# LD-ShouShi-V1_7.net
KiCad netlist of a schematic drawn in Altium Designer
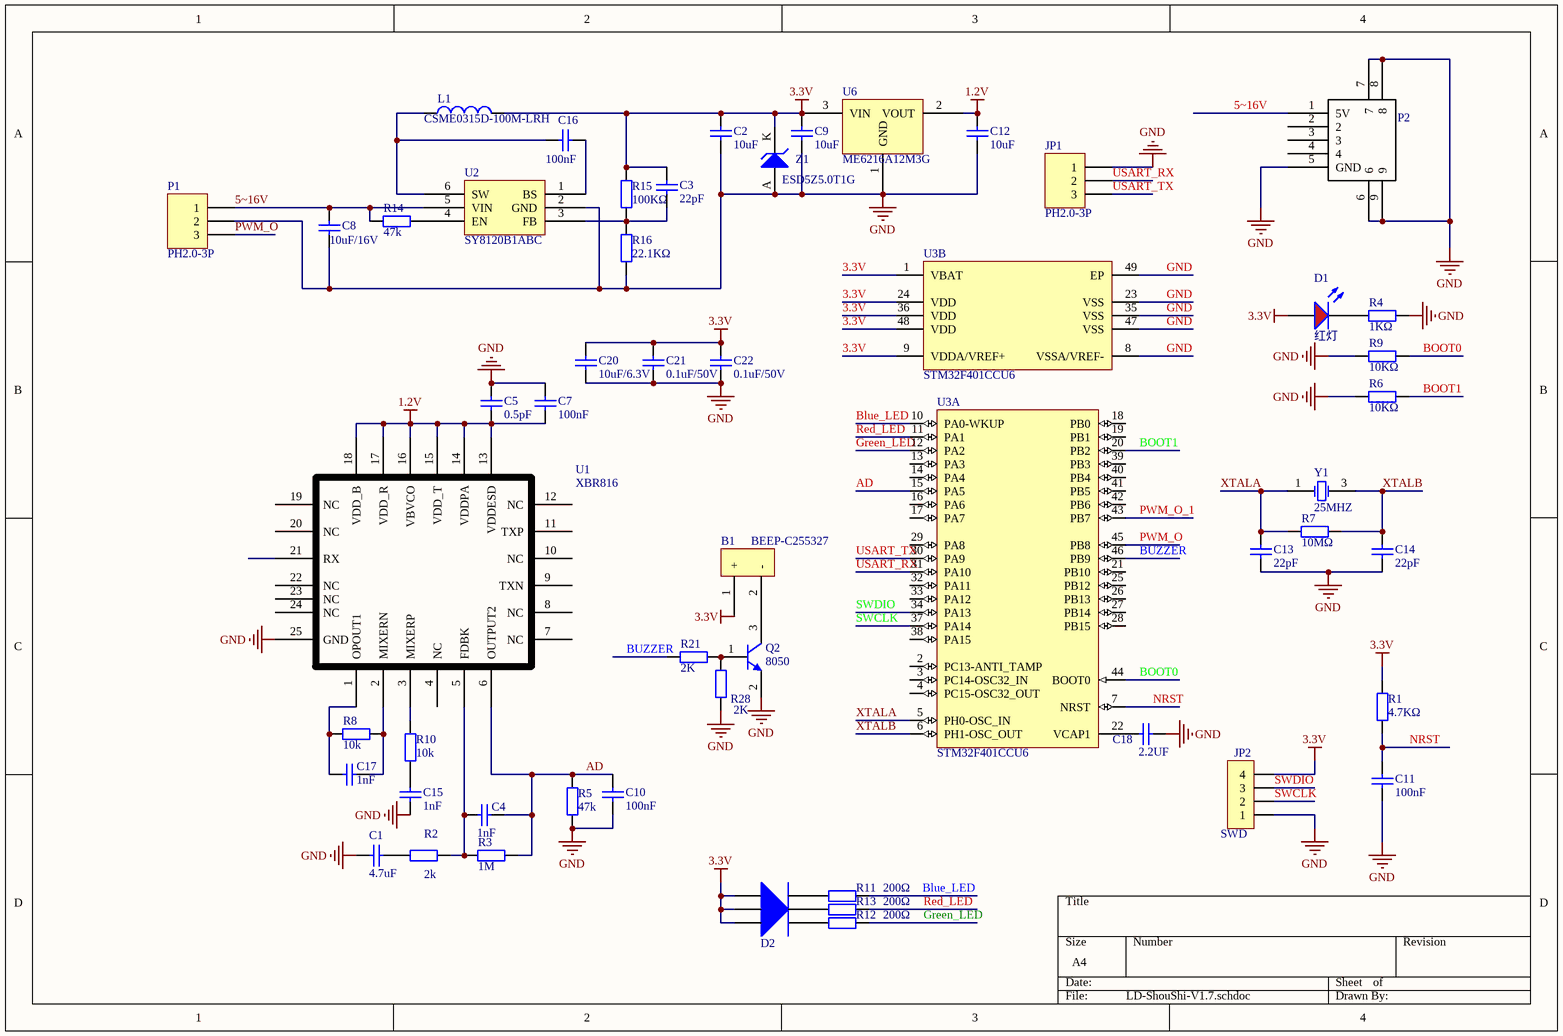
[diagram p0: LD-ShouShi-V1.7.schdoc]

(export (version "E")
  (design (tool "Eeschema 10.0.6"))
  (components
    (comp (ref "B1")
      (value "BEEP-C255327")
      (footprint "C255327-Beep")
      (libsource (lib "PCB_Project1") (part "BEEP"))
    )
    (comp (ref "C1")
      (value "4.7uF")
      (footprint "C0402")
      (description "Capacitor")
      (fields (field (name "PUBLISHER") "Altium Limited"))
      (libsource (lib "Miscellaneous Devices") (part "Cap"))
    )
    (comp (ref "C2")
      (value "10uF")
      (footprint "LC-0402_C")
      (description "贴片电容")
      (libsource (lib "Miscellaneous Devices LC") (part "0402 10uF (106) 20% 6.3V"))
    )
    (comp (ref "C3")
      (value "22pF")
      (footprint "LC-0402_C")
      (description "贴片电容")
      (libsource (lib "Miscellaneous Devices LC") (part "0402 22pF (220) 5% 50V"))
    )
    (comp (ref "C4")
      (value "1nF")
      (footprint "C0402")
      (description "Capacitor")
      (fields (field (name "PUBLISHER") "Altium Limited"))
      (libsource (lib "Miscellaneous Devices") (part "Cap"))
    )
    (comp (ref "C5")
      (value "0.5pF")
      (footprint "C0402")
      (description "Capacitor")
      (fields (field (name "PUBLISHER") "Altium Limited"))
      (libsource (lib "Miscellaneous Devices") (part "Cap"))
    )
    (comp (ref "C7")
      (value "100nF")
      (footprint "C0402")
      (description "Capacitor")
      (fields (field (name "PUBLISHER") "Altium Limited"))
      (libsource (lib "Miscellaneous Devices") (part "Cap"))
    )
    (comp (ref "C8")
      (value "10uF/16V")
      (footprint "C0805")
      (description "Capacitor")
      (fields (field (name "PUBLISHER") "Altium Limited"))
      (libsource (lib "Miscellaneous Devices") (part "Cap"))
    )
    (comp (ref "C9")
      (value "10uF")
      (footprint "LC-0402_C")
      (description "贴片电容")
      (libsource (lib "Miscellaneous Devices LC") (part "0402 10uF (106) 20% 6.3V"))
    )
    (comp (ref "C10")
      (value "100nF")
      (footprint "C0402")
      (description "Capacitor")
      (fields (field (name "PUBLISHER") "Altium Limited"))
      (libsource (lib "Miscellaneous Devices") (part "Cap"))
    )
    (comp (ref "C11")
      (value "100nF")
      (footprint "LC-0402_C")
      (description "贴片电容")
      (libsource (lib "Miscellaneous Devices LC") (part "0402 100nF (104) 10% 16V"))
    )
    (comp (ref "C12")
      (value "10uF")
      (footprint "LC-0402_C")
      (description "贴片电容")
      (libsource (lib "Miscellaneous Devices LC") (part "0402 10uF (106) 20% 6.3V"))
    )
    (comp (ref "C13")
      (value "22pF")
      (footprint "LC-0402_C")
      (description "贴片电容")
      (libsource (lib "Cap") (part "0402 22pF (220) 5% 50V"))
    )
    (comp (ref "C14")
      (value "22pF")
      (footprint "LC-0402_C")
      (description "贴片电容")
      (libsource (lib "Cap") (part "0402 22pF (220) 5% 50V"))
    )
    (comp (ref "C15")
      (value "1nF")
      (footprint "C0402")
      (description "Capacitor")
      (fields (field (name "PUBLISHER") "Altium Limited"))
      (libsource (lib "Miscellaneous Devices") (part "Cap"))
    )
    (comp (ref "C16")
      (value "100nF")
      (footprint "C0402")
      (description "Capacitor")
      (fields (field (name "PUBLISHER") "Altium Limited"))
      (libsource (lib "Miscellaneous Devices") (part "Cap"))
    )
    (comp (ref "C17")
      (value "1nF")
      (footprint "C0402")
      (description "Capacitor")
      (fields (field (name "PUBLISHER") "Altium Limited"))
      (libsource (lib "Miscellaneous Devices") (part "Cap"))
    )
    (comp (ref "C18")
      (value "2.2UF")
      (footprint "LC-0402_C")
      (description "贴片电容")
      (libsource (lib "Cap") (part "0402 2.2nF (222) 10% 50V"))
    )
    (comp (ref "C20")
      (value "10uF/6.3V")
      (footprint "LC-0402_C")
      (description "贴片电容")
      (libsource (lib "Miscellaneous Devices LC") (part "0402 10uF (106) 20% 6.3V"))
    )
    (comp (ref "C21")
      (value "0.1uF/50V")
      (footprint "LC-0402_C")
      (description "贴片电容")
      (libsource (lib "Miscellaneous Devices LC") (part "0402 10uF (106) 20% 6.3V"))
    )
    (comp (ref "C22")
      (value "0.1uF/50V")
      (footprint "LC-0402_C")
      (description "贴片电容")
      (libsource (lib "Miscellaneous Devices LC") (part "0402 10uF (106) 20% 6.3V"))
    )
    (comp (ref "D1")
      (value "红灯")
      (footprint "LC-0603_LED_S1")
      (description "发光二极管")
      (libsource (lib "Miscellaneous Devices LC") (part "0603 红灯"))
    )
    (comp (ref "D2") (value "led三色共阴极灯") (footprint "三色灯") (libsource (lib "微波红外双鉴电路") (part "led三色共阴极灯")))
    (comp (ref "JP1")
      (value "PH2.0-3P")
      (footprint "1X3-2.54")
      (description "Header, 3-Pin")
      (fields (field (name "PUBLISHER") "Altium Limited"))
      (libsource (lib "Miscellaneous Connectors") (part "Header 3"))
    )
    (comp (ref "JP2")
      (value "SWD")
      (footprint "SIP4-2.54")
      (description "4P接插件")
      (fields (field (name "版权归属") "源创客"))
      (libsource (lib "STM32F407_CORE_BOARD") (part "Header 4"))
    )
    (comp (ref "L1")
      (value "CSME0315D-100M-LRH")
      (footprint "PRS3015")
      (description "Inductor")
      (fields (field (name "PUBLISHER") "Altium Limited"))
      (libsource (lib "Miscellaneous Devices") (part "Inductor"))
    )
    (comp (ref "P1")
      (value "PH2.0-3P")
      (footprint "PH2.0-3P")
      (description "Header, 3-Pin")
      (fields (field (name "PUBLISHER") "Altium Limited"))
      (libsource (lib "Miscellaneous Connectors") (part "Header 3"))
    )
    (comp (ref "P2") (value "MINIUSB") (footprint "miniusb") (libsource (lib "调色灯") (part "MINIUSB-M")))
    (comp (ref "Q2")
      (value "8050")
      (footprint "SOT-23")
      (description "NPN General Purpose Amplifier")
      (fields (field (name "PUBLISHER") "Altium Limited"))
      (libsource (lib "圆形报警器NEW-V2.0") (part "2N3904"))
    )
    (comp (ref "R1")
      (value "4.7KΩ")
      (footprint "LC-0402_R")
      (description "贴片电阻")
      (libsource (lib "Miscellaneous Devices LC") (part "0402 4.7KΩ (4701) 1%"))
    )
    (comp (ref "R2")
      (value "2k")
      (footprint "R0402")
      (description "Resistor")
      (fields (field (name "PUBLISHER") "Altium Limited"))
      (libsource (lib "") (part "Res2_2"))
    )
    (comp (ref "R3")
      (value "1M")
      (footprint "R0402")
      (description "Resistor")
      (fields (field (name "PUBLISHER") "Altium Limited"))
      (libsource (lib "") (part "Res2_1"))
    )
    (comp (ref "R4")
      (value "1KΩ")
      (footprint "LC-0402_R")
      (description "贴片电阻")
      (libsource (lib "Miscellaneous Devices LC") (part "0402 1KΩ (1001) 1%"))
    )
    (comp (ref "R5")
      (value "47k")
      (footprint "R0402")
      (description "Resistor")
      (fields (field (name "PUBLISHER") "Altium Limited"))
      (libsource (lib "Miscellaneous Devices") (part "Res2"))
    )
    (comp (ref "R6")
      (value "10KΩ")
      (footprint "LC-0402_R")
      (description "贴片电阻")
      (libsource (lib "Miscellaneous Devices LC") (part "0402 10KΩ (1002) 1%"))
    )
    (comp (ref "R7")
      (value "10MΩ")
      (footprint "LC-0402_R")
      (description "贴片电阻")
      (libsource (lib "Miscellaneous Devices LC") (part "0402 10MΩ (1005) 1%"))
    )
    (comp (ref "R8")
      (value "10k")
      (footprint "R0402")
      (description "Resistor")
      (fields (field (name "PUBLISHER") "Altium Limited"))
      (libsource (lib "") (part "Res2_1"))
    )
    (comp (ref "R9")
      (value "10KΩ")
      (footprint "LC-0402_R")
      (description "贴片电阻")
      (libsource (lib "Miscellaneous Devices LC") (part "0402 10KΩ (1002) 1%"))
    )
    (comp (ref "R10")
      (value "10k")
      (footprint "R0402")
      (description "Resistor")
      (fields (field (name "PUBLISHER") "Altium Limited"))
      (libsource (lib "Miscellaneous Devices") (part "Res2"))
    )
    (comp (ref "R11")
      (value "200Ω")
      (footprint "LC-0402_R")
      (description "贴片电阻")
      (libsource (lib "Miscellaneous Devices LC") (part "0402 200Ω (2000) 1%"))
    )
    (comp (ref "R12")
      (value "200Ω")
      (footprint "LC-0402_R")
      (description "贴片电阻")
      (libsource (lib "Miscellaneous Devices LC") (part "0402 200Ω (2000) 1%"))
    )
    (comp (ref "R13")
      (value "200Ω")
      (footprint "LC-0402_R")
      (description "贴片电阻")
      (libsource (lib "Miscellaneous Devices LC") (part "0402 200Ω (2000) 1%"))
    )
    (comp (ref "R14")
      (value "47k")
      (footprint "R0402")
      (description "Resistor")
      (fields (field (name "PUBLISHER") "Altium Limited"))
      (libsource (lib "") (part "Res2_1"))
    )
    (comp (ref "R15")
      (value "100KΩ")
      (footprint "LC-0402_R")
      (description "贴片电阻")
      (libsource (lib "Miscellaneous Devices LC") (part "0402 100KΩ (1003) 1%"))
    )
    (comp (ref "R16")
      (value "22.1KΩ")
      (footprint "LC-0402_R")
      (description "贴片电阻")
      (libsource (lib "Miscellaneous Devices LC") (part "0402 22KΩ (2202) 1%"))
    )
    (comp (ref "R21")
      (value "2K")
      (footprint "R0402")
      (description "Resistor")
      (fields (field (name "PUBLISHER") "Altium Limited"))
      (libsource (lib "*") (part "Res2"))
    )
    (comp (ref "R28")
      (value "2K")
      (footprint "R0402")
      (description "Resistor")
      (fields (field (name "PUBLISHER") "Altium Limited"))
      (libsource (lib "") (part "Res2_1"))
    )
    (comp (ref "U1") (value "XBR816") (footprint "QFN24-1") (libsource (lib "Schlib1") (part "XBR1000_24_1")))
    (comp (ref "U2") (value "SY8120B1ABC") (footprint "SOT23-6") (libsource (lib "Schlib1") (part "H9108")))
    (comp (ref "U3")
      (value "STM32F401CCU6")
      (footprint "UFQFPN-48_L7.0-W7.0-P0.50-BL-EP")
      (fields (field (name "MANUFACTURER") "STMicroelectronics"))
      (libsource (lib "STMicroelectronics STM32 F4") (part "STM32F401CCU6"))
    )
    (comp (ref "U6") (value "ME6216A12M3G") (footprint "SOT-23") (libsource (lib "Schlib1") (part "SSP6206")))
    (comp (ref "Y1")
      (value "25MHZ")
      (footprint "OSC-SMD_4P-L2.0-W1.6-BL")
      (description "贴片晶振")
      (libsource (lib "CrystalOscillator") (part "SMD-3225_4P  25MHZ 12PF 10PPM"))
    )
    (comp (ref "Z1")
      (value "ESD5Z5.0T1G")
      (footprint "SOD523")
      (description "Zener Diode")
      (fields (field (name "PUBLISHER") "Altium Limited"))
      (libsource (lib "Miscellaneous Devices") (part "D Zener"))
    )
  )
  (nets
    (net (code "1") (name "/5~16V") (class "Default")
      (node (ref "C8") (pin "1") (pinfunction "1_1") (pintype "passive"))
      (node (ref "P1") (pin "1") (pinfunction "1_1") (pintype "passive"))
      (node (ref "P2") (pin "1") (pinfunction "5V_1") (pintype "passive"))
      (node (ref "R14") (pin "2") (pinfunction "2_2") (pintype "passive"))
      (node (ref "U2") (pin "5") (pinfunction "VIN_5") (pintype "passive"))
    )
    (net (code "2") (name "/AD") (class "Default")
      (node (ref "C10") (pin "1") (pinfunction "1_1") (pintype "passive"))
      (node (ref "C4") (pin "1") (pinfunction "1_1") (pintype "passive"))
      (node (ref "R3") (pin "1") (pinfunction "1_1") (pintype "passive"))
      (node (ref "R5") (pin "1") (pinfunction "1_1") (pintype "passive"))
      (node (ref "U1") (pin "6") (pinfunction "OUTPUT2_6") (pintype "passive"))
      (node (ref "U3") (pin "15") (pinfunction "PA5_15") (pintype "bidirectional"))
    )
    (net (code "3") (name "/BOOT0") (class "Default")
      (node (ref "R9") (pin "2") (pinfunction "2_2") (pintype "passive"))
      (node (ref "U3") (pin "44") (pinfunction "BOOT0_44") (pintype "input"))
    )
    (net (code "4") (name "/BOOT1") (class "Default")
      (node (ref "R6") (pin "2") (pinfunction "2_2") (pintype "passive"))
      (node (ref "U3") (pin "20") (pinfunction "PB2_20") (pintype "bidirectional"))
    )
    (net (code "5") (name "/BUZZER") (class "Default")
      (node (ref "R21") (pin "1") (pinfunction "1_1") (pintype "passive"))
      (node (ref "U3") (pin "46") (pinfunction "PB9_46") (pintype "bidirectional"))
    )
    (net (code "6") (name "/Blue_LED") (class "Default")
      (node (ref "R11") (pin "2") (pinfunction "2_2") (pintype "passive"))
      (node (ref "U3") (pin "10") (pinfunction "PA0-WKUP_10") (pintype "bidirectional"))
    )
    (net (code "7") (name "/Green_LED") (class "Default")
      (node (ref "R12") (pin "2") (pinfunction "2_2") (pintype "passive"))
      (node (ref "U3") (pin "12") (pinfunction "PA2_12") (pintype "bidirectional"))
    )
    (net (code "8") (name "/NRST") (class "Default")
      (node (ref "C11") (pin "2") (pinfunction "2_2") (pintype "passive"))
      (node (ref "R1") (pin "1") (pinfunction "1_1") (pintype "passive"))
      (node (ref "U3") (pin "7") (pinfunction "NRST_7") (pintype "bidirectional"))
    )
    (net (code "9") (name "/PWM_O") (class "Default")
      (node (ref "P1") (pin "3") (pinfunction "3_3") (pintype "passive"))
      (node (ref "U3") (pin "45") (pinfunction "PB8_45") (pintype "bidirectional"))
    )
    (net (code "10") (name "/PWM_O_1") (class "Default")
      (node (ref "U3") (pin "43") (pinfunction "PB7_43") (pintype "bidirectional"))
    )
    (net (code "11") (name "/Red_LED") (class "Default")
      (node (ref "R13") (pin "2") (pinfunction "2_2") (pintype "passive"))
      (node (ref "U3") (pin "11") (pinfunction "PA1_11") (pintype "bidirectional"))
    )
    (net (code "12") (name "/SWCLK") (class "Default")
      (node (ref "JP2") (pin "2") (pinfunction "2_2") (pintype "passive"))
      (node (ref "U3") (pin "37") (pinfunction "PA14_37") (pintype "bidirectional"))
    )
    (net (code "13") (name "/SWDIO") (class "Default")
      (node (ref "JP2") (pin "3") (pinfunction "3_3") (pintype "passive"))
      (node (ref "U3") (pin "34") (pinfunction "PA13_34") (pintype "bidirectional"))
    )
    (net (code "14") (name "/USART_RX") (class "Default")
      (node (ref "JP1") (pin "2") (pinfunction "2_2") (pintype "passive"))
      (node (ref "U3") (pin "31") (pinfunction "PA10_31") (pintype "bidirectional"))
    )
    (net (code "15") (name "/USART_TX") (class "Default")
      (node (ref "JP1") (pin "3") (pinfunction "3_3") (pintype "passive"))
      (node (ref "U3") (pin "30") (pinfunction "PA9_30") (pintype "bidirectional"))
    )
    (net (code "16") (name "/XTALA") (class "Default")
      (node (ref "C13") (pin "2") (pinfunction "2_2") (pintype "passive"))
      (node (ref "R7") (pin "1") (pinfunction "1_1") (pintype "passive"))
      (node (ref "U3") (pin "5") (pinfunction "PH0-OSC_IN_5") (pintype "bidirectional"))
      (node (ref "Y1") (pin "1") (pinfunction "OSC1_1") (pintype "passive"))
    )
    (net (code "17") (name "/XTALB") (class "Default")
      (node (ref "C14") (pin "2") (pinfunction "2_2") (pintype "passive"))
      (node (ref "R7") (pin "2") (pinfunction "2_2") (pintype "passive"))
      (node (ref "U3") (pin "6") (pinfunction "PH1-OSC_OUT_6") (pintype "bidirectional"))
      (node (ref "Y1") (pin "3") (pinfunction "OSC2_3") (pintype "passive"))
    )
    (net (code "18") (name "1.2V") (class "Default")
      (node (ref "C12") (pin "2") (pinfunction "2_2") (pintype "passive"))
      (node (ref "C5") (pin "1") (pinfunction "1_1") (pintype "passive"))
      (node (ref "C7") (pin "1") (pinfunction "1_1") (pintype "passive"))
      (node (ref "U1") (pin "13") (pinfunction "VDDESD_13") (pintype "passive"))
      (node (ref "U1") (pin "14") (pinfunction "VDDPA_14") (pintype "passive"))
      (node (ref "U1") (pin "15") (pinfunction "VDD_T_15") (pintype "passive"))
      (node (ref "U1") (pin "16") (pinfunction "VBVCO_16") (pintype "passive"))
      (node (ref "U1") (pin "17") (pinfunction "VDD_R_17") (pintype "passive"))
      (node (ref "U1") (pin "18") (pinfunction "VDD_B_18") (pintype "passive"))
      (node (ref "U6") (pin "2") (pinfunction "VOUT_2") (pintype "passive"))
    )
    (net (code "19") (name "3.3V") (class "Default")
      (node (ref "B1") (pin "1") (pinfunction "+_1") (pintype "passive"))
      (node (ref "C2") (pin "2") (pinfunction "2_2") (pintype "passive"))
      (node (ref "C20") (pin "2") (pinfunction "2_2") (pintype "passive"))
      (node (ref "C21") (pin "2") (pinfunction "2_2") (pintype "passive"))
      (node (ref "C22") (pin "2") (pinfunction "2_2") (pintype "passive"))
      (node (ref "C3") (pin "2") (pinfunction "2_2") (pintype "passive"))
      (node (ref "C9") (pin "2") (pinfunction "2_2") (pintype "passive"))
      (node (ref "D1") (pin "A") (pinfunction "A_A") (pintype "passive"))
      (node (ref "D2") (pin "1") (pinfunction "A+_1") (pintype "passive"))
      (node (ref "D2") (pin "2") (pinfunction "B+_2") (pintype "passive"))
      (node (ref "D2") (pin "3") (pinfunction "C+_3") (pintype "passive"))
      (node (ref "JP2") (pin "4") (pinfunction "4_4") (pintype "passive"))
      (node (ref "L1") (pin "2") (pinfunction "2_2") (pintype "passive"))
      (node (ref "R1") (pin "2") (pinfunction "2_2") (pintype "passive"))
      (node (ref "R15") (pin "2") (pinfunction "2_2") (pintype "passive"))
      (node (ref "U3") (pin "1") (pinfunction "VBAT_1") (pintype "power_in"))
      (node (ref "U3") (pin "24") (pinfunction "VDD_24") (pintype "power_in"))
      (node (ref "U3") (pin "36") (pinfunction "VDD_36") (pintype "power_in"))
      (node (ref "U3") (pin "48") (pinfunction "VDD_48") (pintype "power_in"))
      (node (ref "U3") (pin "9") (pinfunction "VDDA/VREF+_9") (pintype "power_in"))
      (node (ref "U6") (pin "3") (pinfunction "VIN_3") (pintype "passive"))
      (node (ref "Z1") (pin "K") (pinfunction "K_K") (pintype "passive"))
    )
    (net (code "20") (name "GND") (class "Default")
      (node (ref "C1") (pin "2") (pinfunction "2_2") (pintype "passive"))
      (node (ref "C10") (pin "2") (pinfunction "2_2") (pintype "passive"))
      (node (ref "C11") (pin "1") (pinfunction "1_1") (pintype "passive"))
      (node (ref "C12") (pin "1") (pinfunction "1_1") (pintype "passive"))
      (node (ref "C13") (pin "1") (pinfunction "1_1") (pintype "passive"))
      (node (ref "C14") (pin "1") (pinfunction "1_1") (pintype "passive"))
      (node (ref "C15") (pin "1") (pinfunction "1_1") (pintype "passive"))
      (node (ref "C18") (pin "2") (pinfunction "2_2") (pintype "passive"))
      (node (ref "C2") (pin "1") (pinfunction "1_1") (pintype "passive"))
      (node (ref "C20") (pin "1") (pinfunction "1_1") (pintype "passive"))
      (node (ref "C21") (pin "1") (pinfunction "1_1") (pintype "passive"))
      (node (ref "C22") (pin "1") (pinfunction "1_1") (pintype "passive"))
      (node (ref "C5") (pin "2") (pinfunction "2_2") (pintype "passive"))
      (node (ref "C7") (pin "2") (pinfunction "2_2") (pintype "passive"))
      (node (ref "C8") (pin "2") (pinfunction "2_2") (pintype "passive"))
      (node (ref "C9") (pin "1") (pinfunction "1_1") (pintype "passive"))
      (node (ref "JP1") (pin "1") (pinfunction "1_1") (pintype "passive"))
      (node (ref "JP2") (pin "1") (pinfunction "1_1") (pintype "passive"))
      (node (ref "P1") (pin "2") (pinfunction "2_2") (pintype "passive"))
      (node (ref "P2") (pin "5") (pinfunction "GND_5") (pintype "passive"))
      (node (ref "P2") (pin "6") (pinfunction "6_6") (pintype "passive"))
      (node (ref "P2") (pin "7") (pinfunction "7_7") (pintype "passive"))
      (node (ref "P2") (pin "8") (pinfunction "8_8") (pintype "passive"))
      (node (ref "P2") (pin "9") (pinfunction "9_9") (pintype "passive"))
      (node (ref "Q2") (pin "2") (pinfunction "E_2") (pintype "passive"))
      (node (ref "R16") (pin "2") (pinfunction "2_2") (pintype "passive"))
      (node (ref "R28") (pin "1") (pinfunction "1_1") (pintype "passive"))
      (node (ref "R4") (pin "1") (pinfunction "1_1") (pintype "passive"))
      (node (ref "R5") (pin "2") (pinfunction "2_2") (pintype "passive"))
      (node (ref "R6") (pin "1") (pinfunction "1_1") (pintype "passive"))
      (node (ref "R9") (pin "1") (pinfunction "1_1") (pintype "passive"))
      (node (ref "U1") (pin "25") (pinfunction "GND_25") (pintype "passive"))
      (node (ref "U2") (pin "2") (pinfunction "GND_2") (pintype "passive"))
      (node (ref "U3") (pin "23") (pinfunction "VSS_23") (pintype "power_in"))
      (node (ref "U3") (pin "35") (pinfunction "VSS_35") (pintype "power_in"))
      (node (ref "U3") (pin "47") (pinfunction "VSS_47") (pintype "power_in"))
      (node (ref "U3") (pin "49") (pinfunction "EP_49") (pintype "power_in"))
      (node (ref "U3") (pin "8") (pinfunction "VSSA/VREF-_8") (pintype "power_in"))
      (node (ref "U6") (pin "1") (pinfunction "GND_1") (pintype "passive"))
      (node (ref "Z1") (pin "A") (pinfunction "A_A") (pintype "passive"))
    )
    (net (code "21") (name "Net-(B1--)") (class "Default")
      (node (ref "B1") (pin "2") (pinfunction "-_2") (pintype "passive"))
      (node (ref "Q2") (pin "3") (pinfunction "C_3") (pintype "passive"))
    )
    (net (code "22") (name "Net-(C1-Pad1)") (class "Default")
      (node (ref "C1") (pin "1") (pinfunction "1_1") (pintype "passive"))
      (node (ref "R2") (pin "1") (pinfunction "1_1") (pintype "passive"))
    )
    (net (code "23") (name "Net-(C15-Pad2)") (class "Default")
      (node (ref "C15") (pin "2") (pinfunction "2_2") (pintype "passive"))
      (node (ref "R10") (pin "2") (pinfunction "2_2") (pintype "passive"))
    )
    (net (code "24") (name "Net-(D1-PadK)") (class "Default")
      (node (ref "D1") (pin "K") (pinfunction "K_K") (pintype "passive"))
      (node (ref "R4") (pin "2") (pinfunction "2_2") (pintype "passive"))
    )
    (net (code "25") (name "Net-(D2-A-)") (class "Default")
      (node (ref "D2") (pin "4") (pinfunction "A-_4") (pintype "passive"))
      (node (ref "R11") (pin "1") (pinfunction "1_1") (pintype "passive"))
    )
    (net (code "26") (name "Net-(D2-B-)") (class "Default")
      (node (ref "D2") (pin "5") (pinfunction "B-_5") (pintype "passive"))
      (node (ref "R13") (pin "1") (pinfunction "1_1") (pintype "passive"))
    )
    (net (code "27") (name "Net-(D2-C-)") (class "Default")
      (node (ref "D2") (pin "6") (pinfunction "C-_6") (pintype "passive"))
      (node (ref "R12") (pin "1") (pinfunction "1_1") (pintype "passive"))
    )
    (net (code "28") (name "Net-(Q2-B)") (class "Default")
      (node (ref "Q2") (pin "1") (pinfunction "B_1") (pintype "passive"))
      (node (ref "R21") (pin "2") (pinfunction "2_2") (pintype "passive"))
      (node (ref "R28") (pin "2") (pinfunction "2_2") (pintype "passive"))
    )
    (net (code "29") (name "Net-(U1-FDBK)") (class "Default")
      (node (ref "C4") (pin "2") (pinfunction "2_2") (pintype "passive"))
      (node (ref "R2") (pin "2") (pinfunction "2_2") (pintype "passive"))
      (node (ref "R3") (pin "2") (pinfunction "2_2") (pintype "passive"))
      (node (ref "U1") (pin "5") (pinfunction "FDBK_5") (pintype "passive"))
    )
    (net (code "30") (name "Net-(U1-MIXERN)") (class "Default")
      (node (ref "C17") (pin "1") (pinfunction "1_1") (pintype "passive"))
      (node (ref "R8") (pin "1") (pinfunction "1_1") (pintype "passive"))
      (node (ref "U1") (pin "2") (pinfunction "MIXERN_2") (pintype "passive"))
    )
    (net (code "31") (name "Net-(U1-MIXERP)") (class "Default")
      (node (ref "R10") (pin "1") (pinfunction "1_1") (pintype "passive"))
      (node (ref "U1") (pin "3") (pinfunction "MIXERP_3") (pintype "passive"))
    )
    (net (code "32") (name "Net-(U1-OPOUT1)") (class "Default")
      (node (ref "C17") (pin "2") (pinfunction "2_2") (pintype "passive"))
      (node (ref "R8") (pin "2") (pinfunction "2_2") (pintype "passive"))
      (node (ref "U1") (pin "1") (pinfunction "OPOUT1_1") (pintype "passive"))
    )
    (net (code "33") (name "Net-(U2-BS)") (class "Default")
      (node (ref "C16") (pin "2") (pinfunction "2_2") (pintype "passive"))
      (node (ref "U2") (pin "1") (pinfunction "BS_1") (pintype "passive"))
    )
    (net (code "34") (name "Net-(U2-EN)") (class "Default")
      (node (ref "R14") (pin "1") (pinfunction "1_1") (pintype "passive"))
      (node (ref "U2") (pin "4") (pinfunction "EN_4") (pintype "passive"))
    )
    (net (code "35") (name "Net-(U2-FB)") (class "Default")
      (node (ref "C3") (pin "1") (pinfunction "1_1") (pintype "passive"))
      (node (ref "R15") (pin "1") (pinfunction "1_1") (pintype "passive"))
      (node (ref "R16") (pin "1") (pinfunction "1_1") (pintype "passive"))
      (node (ref "U2") (pin "3") (pinfunction "FB_3") (pintype "passive"))
    )
    (net (code "36") (name "Net-(U2-SW)") (class "Default")
      (node (ref "C16") (pin "1") (pinfunction "1_1") (pintype "passive"))
      (node (ref "L1") (pin "1") (pinfunction "1_1") (pintype "passive"))
      (node (ref "U2") (pin "6") (pinfunction "SW_6") (pintype "passive"))
    )
    (net (code "37") (name "Net-(U3A-VCAP1)") (class "Default")
      (node (ref "C18") (pin "1") (pinfunction "1_1") (pintype "passive"))
      (node (ref "U3") (pin "22") (pinfunction "VCAP1_22") (pintype "power_in"))
    )
    (net (code "38") (name "unconnected-(P2-Pad2)") (class "Default")
      (node (ref "P2") (pin "2") (pinfunction "2_2") (pintype "passive"))
    )
    (net (code "39") (name "unconnected-(P2-Pad3)") (class "Default")
      (node (ref "P2") (pin "3") (pinfunction "3_3") (pintype "passive"))
    )
    (net (code "40") (name "unconnected-(P2-Pad4)") (class "Default")
      (node (ref "P2") (pin "4") (pinfunction "4_4") (pintype "passive"))
    )
    (net (code "41") (name "unconnected-(U1-NC-Pad4)") (class "Default")
      (node (ref "U1") (pin "4") (pinfunction "NC_4") (pintype "passive"))
    )
    (net (code "42") (name "unconnected-(U1-NC-Pad7)") (class "Default")
      (node (ref "U1") (pin "7") (pinfunction "NC_7") (pintype "passive"))
    )
    (net (code "43") (name "unconnected-(U1-NC-Pad8)") (class "Default")
      (node (ref "U1") (pin "8") (pinfunction "NC_8") (pintype "passive"))
    )
    (net (code "44") (name "unconnected-(U1-NC-Pad10)") (class "Default")
      (node (ref "U1") (pin "10") (pinfunction "NC_10") (pintype "passive"))
    )
    (net (code "45") (name "unconnected-(U1-NC-Pad12)") (class "Default")
      (node (ref "U1") (pin "12") (pinfunction "NC_12") (pintype "passive"))
    )
    (net (code "46") (name "unconnected-(U1-NC-Pad19)") (class "Default")
      (node (ref "U1") (pin "19") (pinfunction "NC_19") (pintype "passive"))
    )
    (net (code "47") (name "unconnected-(U1-NC-Pad20)") (class "Default")
      (node (ref "U1") (pin "20") (pinfunction "NC_20") (pintype "passive"))
    )
    (net (code "48") (name "unconnected-(U1-NC-Pad22)") (class "Default")
      (node (ref "U1") (pin "22") (pinfunction "NC_22") (pintype "passive"))
    )
    (net (code "49") (name "unconnected-(U1-NC-Pad23)") (class "Default")
      (node (ref "U1") (pin "23") (pinfunction "NC_23") (pintype "passive"))
    )
    (net (code "50") (name "unconnected-(U1-NC-Pad24)") (class "Default")
      (node (ref "U1") (pin "24") (pinfunction "NC_24") (pintype "passive"))
    )
    (net (code "51") (name "unconnected-(U1-RX-Pad21)") (class "Default")
      (node (ref "U1") (pin "21") (pinfunction "RX_21") (pintype "passive"))
    )
    (net (code "52") (name "unconnected-(U1-TXN-Pad9)") (class "Default")
      (node (ref "U1") (pin "9") (pinfunction "TXN_9") (pintype "passive"))
    )
    (net (code "53") (name "unconnected-(U1-TXP-Pad11)") (class "Default")
      (node (ref "U1") (pin "11") (pinfunction "TXP_11") (pintype "passive"))
    )
    (net (code "54") (name "unconnected-(U3A-PA3-Pad13)") (class "Default")
      (node (ref "U3") (pin "13") (pinfunction "PA3_13") (pintype "bidirectional"))
    )
    (net (code "55") (name "unconnected-(U3A-PA4-Pad14)") (class "Default")
      (node (ref "U3") (pin "14") (pinfunction "PA4_14") (pintype "bidirectional"))
    )
    (net (code "56") (name "unconnected-(U3A-PA6-Pad16)") (class "Default")
      (node (ref "U3") (pin "16") (pinfunction "PA6_16") (pintype "bidirectional"))
    )
    (net (code "57") (name "unconnected-(U3A-PA7-Pad17)") (class "Default")
      (node (ref "U3") (pin "17") (pinfunction "PA7_17") (pintype "bidirectional"))
    )
    (net (code "58") (name "unconnected-(U3A-PA8-Pad29)") (class "Default")
      (node (ref "U3") (pin "29") (pinfunction "PA8_29") (pintype "bidirectional"))
    )
    (net (code "59") (name "unconnected-(U3A-PA11-Pad32)") (class "Default")
      (node (ref "U3") (pin "32") (pinfunction "PA11_32") (pintype "bidirectional"))
    )
    (net (code "60") (name "unconnected-(U3A-PA12-Pad33)") (class "Default")
      (node (ref "U3") (pin "33") (pinfunction "PA12_33") (pintype "bidirectional"))
    )
    (net (code "61") (name "unconnected-(U3A-PA15-Pad38)") (class "Default")
      (node (ref "U3") (pin "38") (pinfunction "PA15_38") (pintype "bidirectional"))
    )
    (net (code "62") (name "unconnected-(U3A-PB0-Pad18)") (class "Default")
      (node (ref "U3") (pin "18") (pinfunction "PB0_18") (pintype "bidirectional"))
    )
    (net (code "63") (name "unconnected-(U3A-PB1-Pad19)") (class "Default")
      (node (ref "U3") (pin "19") (pinfunction "PB1_19") (pintype "bidirectional"))
    )
    (net (code "64") (name "unconnected-(U3A-PB3-Pad39)") (class "Default")
      (node (ref "U3") (pin "39") (pinfunction "PB3_39") (pintype "bidirectional"))
    )
    (net (code "65") (name "unconnected-(U3A-PB4-Pad40)") (class "Default")
      (node (ref "U3") (pin "40") (pinfunction "PB4_40") (pintype "bidirectional"))
    )
    (net (code "66") (name "unconnected-(U3A-PB5-Pad41)") (class "Default")
      (node (ref "U3") (pin "41") (pinfunction "PB5_41") (pintype "bidirectional"))
    )
    (net (code "67") (name "unconnected-(U3A-PB6-Pad42)") (class "Default")
      (node (ref "U3") (pin "42") (pinfunction "PB6_42") (pintype "bidirectional"))
    )
    (net (code "68") (name "unconnected-(U3A-PB10-Pad21)") (class "Default")
      (node (ref "U3") (pin "21") (pinfunction "PB10_21") (pintype "bidirectional"))
    )
    (net (code "69") (name "unconnected-(U3A-PB12-Pad25)") (class "Default")
      (node (ref "U3") (pin "25") (pinfunction "PB12_25") (pintype "bidirectional"))
    )
    (net (code "70") (name "unconnected-(U3A-PB13-Pad26)") (class "Default")
      (node (ref "U3") (pin "26") (pinfunction "PB13_26") (pintype "bidirectional"))
    )
    (net (code "71") (name "unconnected-(U3A-PB14-Pad27)") (class "Default")
      (node (ref "U3") (pin "27") (pinfunction "PB14_27") (pintype "bidirectional"))
    )
    (net (code "72") (name "unconnected-(U3A-PB15-Pad28)") (class "Default")
      (node (ref "U3") (pin "28") (pinfunction "PB15_28") (pintype "bidirectional"))
    )
    (net (code "73") (name "unconnected-(U3A-PC13-ANTI_TAMP-Pad2)") (class "Default")
      (node (ref "U3") (pin "2") (pinfunction "PC13-ANTI_TAMP_2") (pintype "bidirectional"))
    )
    (net (code "74") (name "unconnected-(U3A-PC14-OSC32_IN-Pad3)") (class "Default")
      (node (ref "U3") (pin "3") (pinfunction "PC14-OSC32_IN_3") (pintype "bidirectional"))
    )
    (net (code "75") (name "unconnected-(U3A-PC15-OSC32_OUT-Pad4)") (class "Default")
      (node (ref "U3") (pin "4") (pinfunction "PC15-OSC32_OUT_4") (pintype "bidirectional"))
    )
  )
)
